# 3Dheater1.net
KiCad netlist of a schematic drawn in Altium Designer
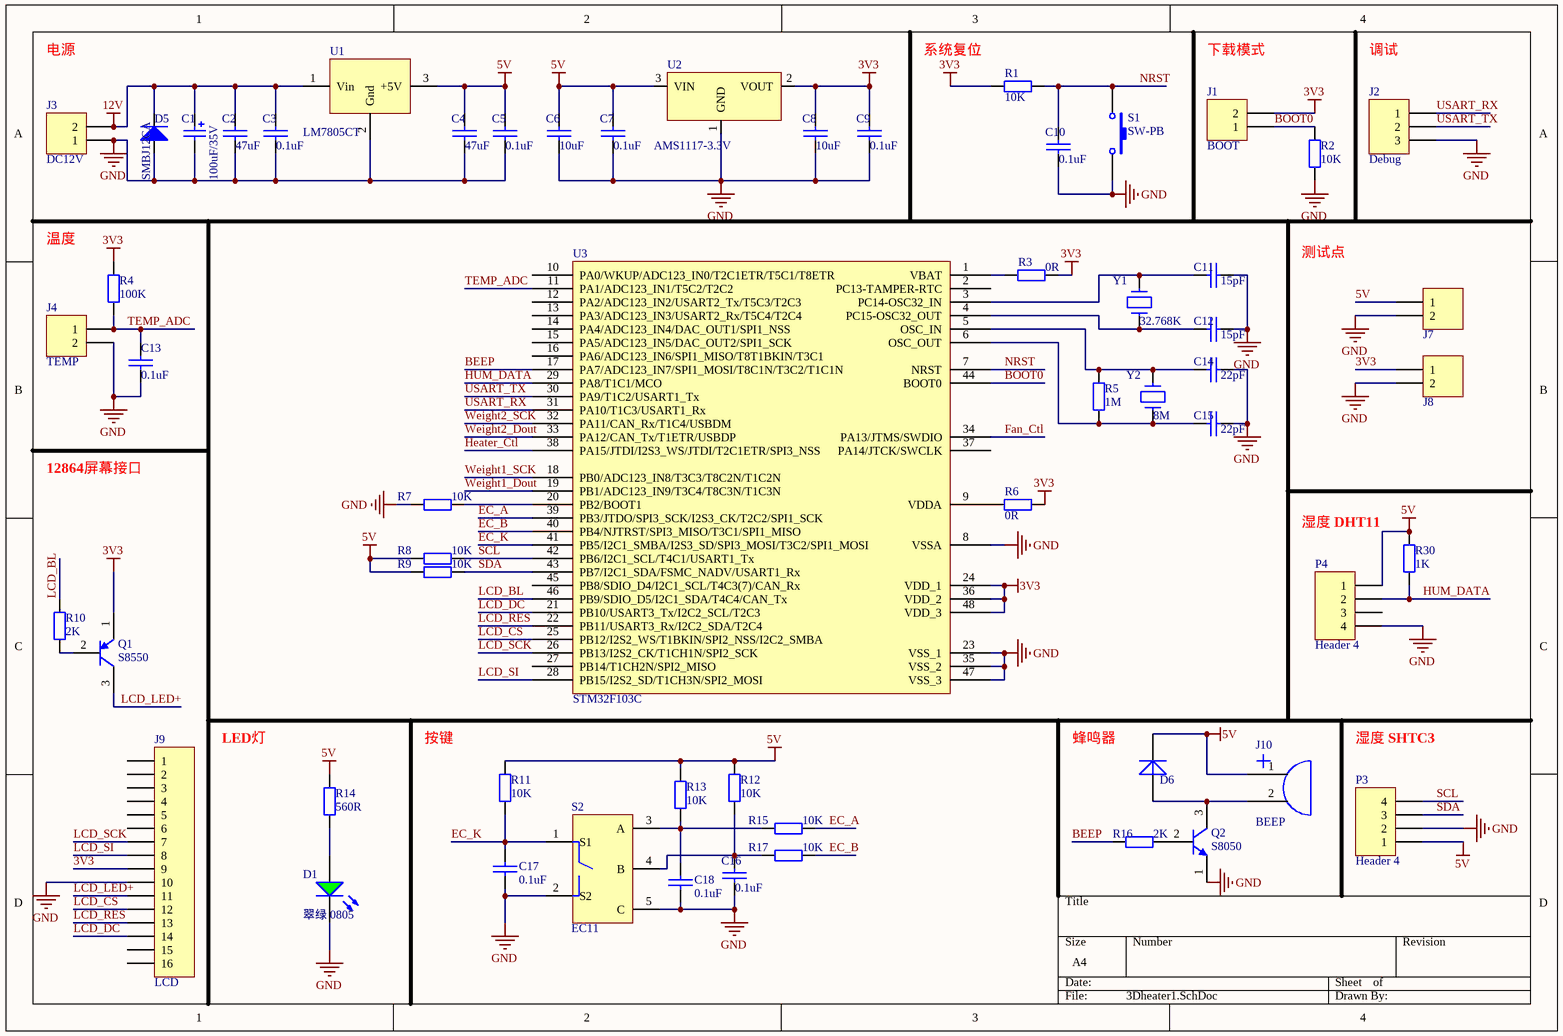
[diagram p0: 3Dheater1.SchDoc]

(export (version "E")
  (design (tool "Eeschema 10.0.6"))
  (components
    (comp (ref "C1")
      (value "100uF/35V")
      (footprint "3Dheater:ELCO Case D")
      (description "RO ELCO 100uF 20% 35V CASE-D EEEFP PAN")
      (libsource (lib "3Dheater") (part "Capacitor Polarity"))
    )
    (comp (ref "C2")
      (value "47uF")
      (footprint "1206")
      (description "Capacitor")
      (libsource (lib "Miscellaneous Devices") (part "CAP"))
    )
    (comp (ref "C3")
      (value "0.1uF")
      (footprint "C0805")
      (description "Capacitor")
      (libsource (lib "Miscellaneous Devices") (part "CAP"))
    )
    (comp (ref "C4")
      (value "47uF")
      (footprint "C0805")
      (description "Capacitor")
      (libsource (lib "Miscellaneous Devices") (part "CAP"))
    )
    (comp (ref "C5")
      (value "0.1uF")
      (footprint "C0805")
      (description "Capacitor")
      (libsource (lib "Miscellaneous Devices") (part "CAP"))
    )
    (comp (ref "C6")
      (value "10uF")
      (footprint "C0805")
      (description "Capacitor")
      (libsource (lib "Miscellaneous Devices") (part "CAP"))
    )
    (comp (ref "C7")
      (value "0.1uF")
      (footprint "C0805")
      (description "Capacitor")
      (libsource (lib "Miscellaneous Devices") (part "CAP"))
    )
    (comp (ref "C8")
      (value "10uF")
      (footprint "C0805")
      (description "Capacitor")
      (libsource (lib "Miscellaneous Devices") (part "CAP"))
    )
    (comp (ref "C9")
      (value "0.1uF")
      (footprint "C0805")
      (description "Capacitor")
      (libsource (lib "Miscellaneous Devices") (part "CAP"))
    )
    (comp (ref "C10")
      (value "0.1uF")
      (footprint "C0805")
      (description "Capacitor")
      (libsource (lib "Miscellaneous Devices") (part "CAP"))
    )
    (comp (ref "C11")
      (value "15pF")
      (footprint "C0805")
      (description "Capacitor")
      (libsource (lib "Miscellaneous Devices") (part "CAP"))
    )
    (comp (ref "C12")
      (value "15pF")
      (footprint "C0805")
      (description "Capacitor")
      (libsource (lib "Miscellaneous Devices") (part "CAP"))
    )
    (comp (ref "C13")
      (value "0.1uF")
      (footprint "C0805")
      (description "Capacitor")
      (libsource (lib "Miscellaneous Devices") (part "CAP"))
    )
    (comp (ref "C14")
      (value "22pF")
      (footprint "C0805")
      (description "Capacitor")
      (libsource (lib "Miscellaneous Devices") (part "CAP"))
    )
    (comp (ref "C15")
      (value "22pF")
      (footprint "C0805")
      (description "Capacitor")
      (libsource (lib "Miscellaneous Devices") (part "CAP"))
    )
    (comp (ref "C16")
      (value "0.1uF")
      (footprint "C0805")
      (description "Capacitor")
      (libsource (lib "Miscellaneous Devices") (part "CAP"))
    )
    (comp (ref "C17")
      (value "0.1uF")
      (footprint "C0805")
      (description "Capacitor")
      (libsource (lib "Miscellaneous Devices") (part "CAP"))
    )
    (comp (ref "C18")
      (value "0.1uF")
      (footprint "C0805")
      (description "Capacitor")
      (libsource (lib "Miscellaneous Devices") (part "CAP"))
    )
    (comp (ref "D1")
      (value "翠绿 0805")
      (footprint "0805_LED_S1")
      (description "发光二极管")
      (libsource (lib "Miscellaneous Devices LC") (part "0805 翠绿"))
    )
    (comp (ref "D5")
      (value "TVS")
      (footprint "DO214AA (SMB)")
      (description "TVS保护")
      (fields (field (name "TYPE") "SMBJ12CA") (field (name "PUBLISHER") "Altium Limited"))
      (libsource (lib "fszhang") (part "TVS"))
    )
    (comp (ref "D6")
      (value "S1G")
      (footprint "DO214AC (SMA)")
      (description "RO DIODE S1G DO-214AC")
      (libsource (lib "Database_Faber") (part "Diode"))
    )
    (comp (ref "J1")
      (value "BOOT")
      (footprint "HDR1X2")
      (description "Header, 2-Pin, Right Angle")
      (fields (field (name "PUBLISHER") "Altium Limited"))
      (libsource (lib "") (part "Header 2H_1"))
    )
    (comp (ref "J2")
      (value "Debug")
      (footprint "HDR1X3")
      (description "接插件")
      (fields (field (name "PUBLISHER") "Altium Limited"))
      (libsource (lib "fszhang") (part "Header 3"))
    )
    (comp (ref "J3")
      (value "DC12V")
      (footprint "HDR1X2_396")
      (description "接插件")
      (fields (field (name "PUBLISHER") "Altium Limited"))
      (libsource (lib "") (part "Header 2_1"))
    )
    (comp (ref "J4")
      (value "TEMP")
      (footprint "HDR1X2")
      (description "Header, 2-Pin, Right Angle")
      (fields (field (name "PUBLISHER") "Altium Limited"))
      (libsource (lib "Miscellaneous Connectors") (part "Header 2H"))
    )
    (comp (ref "J7")
      (value "Header 2")
      (footprint "HDR1X2")
      (description "接插件")
      (fields (field (name "PUBLISHER") "Altium Limited"))
      (libsource (lib "fszhang") (part "Header 2"))
    )
    (comp (ref "J8")
      (value "Header 2")
      (footprint "HDR1X2")
      (description "接插件")
      (fields (field (name "PUBLISHER") "Altium Limited"))
      (libsource (lib "fszhang") (part "Header 2"))
    )
    (comp (ref "J9")
      (value "LCD")
      (footprint "LCD12864")
      (description "Header, 16-Pin")
      (fields (field (name "PUBLISHER") "Altium Limited"))
      (libsource (lib "3Dheater") (part "Header 16"))
    )
    (comp (ref "J10")
      (value "BEEP")
      (footprint "Explorer STM32F407封装库:BELL-5")
      (description "蜂鸣器")
      (libsource (lib "fszhang") (part "BEEP"))
    )
    (comp (ref "P3")
      (value "Header 4")
      (footprint "HDR1X4")
      (description "Header, 4-Pin")
      (fields (field (name "PUBLISHER") "Altium Limited"))
      (libsource (lib "Miscellaneous Connectors") (part "Header 4"))
    )
    (comp (ref "P4")
      (value "Header 4")
      (footprint "HDR1X4")
      (description "Header, 4-Pin")
      (fields (field (name "PUBLISHER") "Altium Limited"))
      (libsource (lib "") (part "Header 4_1"))
    )
    (comp (ref "Q1")
      (value "S8550")
      (footprint "Miscellaneous Devices LC:SOT-23-3L")
      (description "PNP三极管")
      (fields (field (name "PUBLISHER") "Altium Limited"))
      (libsource (lib "fszhang") (part "S8550"))
    )
    (comp (ref "Q2")
      (value "S8050")
      (footprint "Miscellaneous Devices LC:SOT-23-3L")
      (description "NPN三极管")
      (fields (field (name "PUBLISHER") "Altium Limited"))
      (libsource (lib "fszhang") (part "S8050"))
    )
    (comp (ref "R1")
      (value "10K")
      (footprint "R0805")
      (description "贴片电阻")
      (fields (field (name "PUBLISHER") "Altium Limited"))
      (libsource (lib "") (part "Res1_1"))
    )
    (comp (ref "R2")
      (value "10K")
      (footprint "R0805")
      (description "贴片电阻")
      (fields (field (name "PUBLISHER") "Altium Limited"))
      (libsource (lib "") (part "Res1_3"))
    )
    (comp (ref "R3")
      (value "0R")
      (footprint "R0805")
      (description "贴片电阻")
      (fields (field (name "PUBLISHER") "Altium Limited"))
      (libsource (lib "") (part "Res1_1"))
    )
    (comp (ref "R4")
      (value "100K")
      (footprint "R0805")
      (description "贴片电阻")
      (fields (field (name "PUBLISHER") "Altium Limited"))
      (libsource (lib "") (part "Res1_3"))
    )
    (comp (ref "R5")
      (value "1M")
      (footprint "R0805")
      (description "贴片电阻")
      (fields (field (name "PUBLISHER") "Altium Limited"))
      (libsource (lib "") (part "Res1_2"))
    )
    (comp (ref "R6")
      (value "0R")
      (footprint "R0805")
      (description "贴片电阻")
      (fields (field (name "PUBLISHER") "Altium Limited"))
      (libsource (lib "") (part "Res1_1"))
    )
    (comp (ref "R7")
      (value "10K")
      (footprint "R0805")
      (description "贴片电阻")
      (fields (field (name "PUBLISHER") "Altium Limited"))
      (libsource (lib "") (part "Res1_1"))
    )
    (comp (ref "R8")
      (value "10K")
      (footprint "R0805")
      (description "贴片电阻")
      (fields (field (name "PUBLISHER") "Altium Limited"))
      (libsource (lib "fszhang") (part "Res1"))
    )
    (comp (ref "R9")
      (value "10K")
      (footprint "R0805")
      (description "贴片电阻")
      (fields (field (name "PUBLISHER") "Altium Limited"))
      (libsource (lib "fszhang") (part "Res1"))
    )
    (comp (ref "R10")
      (value "2K")
      (footprint "R0805")
      (description "贴片电阻")
      (fields (field (name "PUBLISHER") "Altium Limited"))
      (libsource (lib "") (part "Res1_3"))
    )
    (comp (ref "R11")
      (value "10K")
      (footprint "R0805")
      (description "贴片电阻")
      (fields (field (name "PUBLISHER") "Altium Limited"))
      (libsource (lib "") (part "Res1_2"))
    )
    (comp (ref "R12")
      (value "10K")
      (footprint "R0805")
      (description "贴片电阻")
      (fields (field (name "PUBLISHER") "Altium Limited"))
      (libsource (lib "") (part "Res1_2"))
    )
    (comp (ref "R13")
      (value "10K")
      (footprint "R0805")
      (description "贴片电阻")
      (fields (field (name "PUBLISHER") "Altium Limited"))
      (libsource (lib "") (part "Res1_2"))
    )
    (comp (ref "R14")
      (value "560R")
      (footprint "R0805")
      (description "贴片电阻")
      (fields (field (name "PUBLISHER") "Altium Limited"))
      (libsource (lib "") (part "Res1_2"))
    )
    (comp (ref "R15")
      (value "10K")
      (footprint "R0805")
      (description "贴片电阻")
      (fields (field (name "PUBLISHER") "Altium Limited"))
      (libsource (lib "") (part "Res1_1"))
    )
    (comp (ref "R16")
      (value "2K")
      (footprint "R0805")
      (description "贴片电阻")
      (fields (field (name "PUBLISHER") "Altium Limited"))
      (libsource (lib "") (part "Res1_1"))
    )
    (comp (ref "R17")
      (value "10K")
      (footprint "R0805")
      (description "贴片电阻")
      (fields (field (name "PUBLISHER") "Altium Limited"))
      (libsource (lib "") (part "Res1_1"))
    )
    (comp (ref "R30")
      (value "1K")
      (footprint "R0805")
      (description "贴片电阻")
      (fields (field (name "PUBLISHER") "Altium Limited"))
      (libsource (lib "") (part "Res1_3"))
    )
    (comp (ref "S1")
      (value "SW-PB")
      (footprint "SW-PB2")
      (description "微动开关")
      (fields (field (name "PUBLISHER") "Altium Limited"))
      (libsource (lib "fszhang") (part "SW-PB"))
    )
    (comp (ref "S2")
      (value "EC11")
      (footprint "EC11")
      (description "旋转编码器")
      (libsource (lib "liuxiaolong") (part "EC11"))
    )
    (comp (ref "U1")
      (value "LM7805CT")
      (footprint "TO-252-2-180")
      (libsource (lib "3Dheater") (part "LM7805CT"))
    )
    (comp (ref "U2")
      (value "AMS1117-3.3V")
      (footprint "Miscellaneous Devices LC:SOT-223")
      (libsource (lib "Miscellaneous Devices") (part "LM1117"))
    )
    (comp (ref "U3")
      (value "STM32F103C")
      (footprint "LQFP48_L")
      (description "STM32单片机48引脚")
      (libsource (lib "fszhang") (part "STM32F103C"))
    )
    (comp (ref "Y1")
      (value "32.768K")
      (footprint "XTAL32")
      (description "Crystal")
      (libsource (lib "Miscellaneous Devices") (part "CRYSTAL"))
    )
    (comp (ref "Y2")
      (value "8M")
      (footprint "XTAL_US")
      (description "Crystal")
      (libsource (lib "Miscellaneous Devices") (part "CRYSTAL"))
    )
  )
  (nets
    (net (code "1") (name "/BEEP") (class "Default")
      (node (ref "R16") (pin "2") (pinfunction "2_2") (pintype "passive"))
      (node (ref "U3") (pin "17") (pinfunction "PA7/ADC123_IN7/SPI1_MOSI/T8C1N/T3C2/T1C1N_17") (pintype "passive"))
    )
    (net (code "2") (name "/BOOT0") (class "Default")
      (node (ref "J1") (pin "1") (pinfunction "1_1") (pintype "passive"))
      (node (ref "R2") (pin "1") (pinfunction "1_1") (pintype "passive"))
      (node (ref "U3") (pin "44") (pinfunction "BOOT0_44") (pintype "passive"))
    )
    (net (code "3") (name "/EC_A") (class "Default")
      (node (ref "R15") (pin "1") (pinfunction "1_1") (pintype "passive"))
      (node (ref "U3") (pin "39") (pinfunction "PB3/JTDO/SPI3_SCK/I2S3_CK/T2C2/SPI1_SCK_39") (pintype "passive"))
    )
    (net (code "4") (name "/EC_B") (class "Default")
      (node (ref "R17") (pin "1") (pinfunction "1_1") (pintype "passive"))
      (node (ref "U3") (pin "40") (pinfunction "PB4/NJTRST/SPI3_MISO/T3C1/SPI1_MISO_40") (pintype "passive"))
    )
    (net (code "5") (name "/EC_K") (class "Default")
      (node (ref "C17") (pin "2") (pinfunction "2_2") (pintype "passive"))
      (node (ref "R11") (pin "1") (pinfunction "1_1") (pintype "passive"))
      (node (ref "S2") (pin "1") (pinfunction "S1_1") (pintype "passive"))
      (node (ref "U3") (pin "41") (pinfunction "PB5/I2C1_SMBA/I2S3_SD/SPI3_MOSI/T3C2/SPI1_MOSI_41") (pintype "passive"))
    )
    (net (code "6") (name "/Fan_Ctl") (class "Default")
      (node (ref "U3") (pin "34") (pinfunction "PA13/JTMS/SWDIO_34") (pintype "passive"))
    )
    (net (code "7") (name "/HUM_DATA") (class "Default")
      (node (ref "P4") (pin "2") (pinfunction "2_2") (pintype "passive"))
      (node (ref "R30") (pin "2") (pinfunction "2_2") (pintype "passive"))
      (node (ref "U3") (pin "29") (pinfunction "PA8/T1C1/MCO_29") (pintype "passive"))
    )
    (net (code "8") (name "/Heater_Ctl") (class "Default")
      (node (ref "U3") (pin "38") (pinfunction "PA15/JTDI/I2S3_WS/JTDI/T2C1ETR/SPI3_NSS_38") (pintype "passive"))
    )
    (net (code "9") (name "/LCD_BL") (class "Default")
      (node (ref "R10") (pin "1") (pinfunction "1_1") (pintype "passive"))
      (node (ref "U3") (pin "46") (pinfunction "PB9/SDIO_D5/I2C1_SDA/T4C4/CAN_Tx_46") (pintype "passive"))
    )
    (net (code "10") (name "/LCD_CS") (class "Default")
      (node (ref "J9") (pin "12") (pinfunction "12_12") (pintype "passive"))
      (node (ref "U3") (pin "25") (pinfunction "PB12/I2S2_WS/T1BKIN/SPI2_NSS/I2C2_SMBA_25") (pintype "passive"))
    )
    (net (code "11") (name "/LCD_DC") (class "Default")
      (node (ref "J9") (pin "14") (pinfunction "14_14") (pintype "passive"))
      (node (ref "U3") (pin "21") (pinfunction "PB10/USART3_Tx/I2C2_SCL/T2C3_21") (pintype "passive"))
    )
    (net (code "12") (name "/LCD_LED+") (class "Default")
      (node (ref "J9") (pin "11") (pinfunction "11_11") (pintype "passive"))
      (node (ref "Q1") (pin "3") (pinfunction "C_3") (pintype "passive"))
    )
    (net (code "13") (name "/LCD_RES") (class "Default")
      (node (ref "J9") (pin "13") (pinfunction "13_13") (pintype "passive"))
      (node (ref "U3") (pin "22") (pinfunction "PB11/USART3_Rx/I2C2_SDA/T2C4_22") (pintype "passive"))
    )
    (net (code "14") (name "/LCD_SCK") (class "Default")
      (node (ref "J9") (pin "7") (pinfunction "7_7") (pintype "passive"))
      (node (ref "U3") (pin "26") (pinfunction "PB13/I2S2_CK/T1CH1N/SPI2_SCK_26") (pintype "passive"))
    )
    (net (code "15") (name "/LCD_SI") (class "Default")
      (node (ref "J9") (pin "8") (pinfunction "8_8") (pintype "passive"))
      (node (ref "U3") (pin "28") (pinfunction "PB15/I2S2_SD/T1CH3N/SPI2_MOSI_28") (pintype "passive"))
    )
    (net (code "16") (name "/NRST") (class "Default")
      (node (ref "C10") (pin "2") (pinfunction "2_2") (pintype "passive"))
      (node (ref "R1") (pin "1") (pinfunction "1_1") (pintype "passive"))
      (node (ref "S1") (pin "1") (pinfunction "1_1") (pintype "passive"))
      (node (ref "U3") (pin "7") (pinfunction "NRST_7") (pintype "passive"))
    )
    (net (code "17") (name "/SCL") (class "Default")
      (node (ref "P3") (pin "4") (pinfunction "4_4") (pintype "passive"))
      (node (ref "R8") (pin "2") (pinfunction "2_2") (pintype "passive"))
      (node (ref "U3") (pin "42") (pinfunction "PB6/I2C1_SCL/T4C1/USART1_Tx_42") (pintype "passive"))
    )
    (net (code "18") (name "/SDA") (class "Default")
      (node (ref "P3") (pin "3") (pinfunction "3_3") (pintype "passive"))
      (node (ref "R9") (pin "2") (pinfunction "2_2") (pintype "passive"))
      (node (ref "U3") (pin "43") (pinfunction "PB7/I2C1_SDA/FSMC_NADV/USART1_Rx_43") (pintype "passive"))
    )
    (net (code "19") (name "/TEMP_ADC") (class "Default")
      (node (ref "C13") (pin "2") (pinfunction "2_2") (pintype "passive"))
      (node (ref "J4") (pin "1") (pinfunction "1_1") (pintype "passive"))
      (node (ref "R4") (pin "2") (pinfunction "2_2") (pintype "passive"))
      (node (ref "U3") (pin "11") (pinfunction "PA1/ADC123_IN1/T5C2/T2C2_11") (pintype "passive"))
    )
    (net (code "20") (name "/USART_RX") (class "Default")
      (node (ref "J2") (pin "1") (pinfunction "1_1") (pintype "passive"))
      (node (ref "U3") (pin "31") (pinfunction "PA10/T1C3/USART1_Rx_31") (pintype "passive"))
    )
    (net (code "21") (name "/USART_TX") (class "Default")
      (node (ref "J2") (pin "2") (pinfunction "2_2") (pintype "passive"))
      (node (ref "U3") (pin "30") (pinfunction "PA9/T1C2/USART1_Tx_30") (pintype "passive"))
    )
    (net (code "22") (name "/Weight1_Dout") (class "Default")
      (node (ref "U3") (pin "19") (pinfunction "PB1/ADC123_IN9/T3C4/T8C3N/T1C3N_19") (pintype "passive"))
    )
    (net (code "23") (name "/Weight1_SCK") (class "Default")
      (node (ref "U3") (pin "18") (pinfunction "PB0/ADC123_IN8/T3C3/T8C2N/T1C2N_18") (pintype "passive"))
    )
    (net (code "24") (name "/Weight2_Dout") (class "Default")
      (node (ref "U3") (pin "33") (pinfunction "PA12/CAN_Tx/T1ETR/USBDP_33") (pintype "passive"))
    )
    (net (code "25") (name "/Weight2_SCK") (class "Default")
      (node (ref "U3") (pin "32") (pinfunction "PA11/CAN_Rx/T1C4/USBDM_32") (pintype "passive"))
    )
    (net (code "26") (name "3V3") (class "Default")
      (node (ref "C8") (pin "2") (pinfunction "2_2") (pintype "passive"))
      (node (ref "C9") (pin "2") (pinfunction "2_2") (pintype "passive"))
      (node (ref "J1") (pin "2") (pinfunction "2_2") (pintype "passive"))
      (node (ref "J8") (pin "1") (pinfunction "1_1") (pintype "passive"))
      (node (ref "J9") (pin "9") (pinfunction "9_9") (pintype "passive"))
      (node (ref "Q1") (pin "1") (pinfunction "E_1") (pintype "passive"))
      (node (ref "R1") (pin "2") (pinfunction "2_2") (pintype "passive"))
      (node (ref "R3") (pin "1") (pinfunction "1_1") (pintype "passive"))
      (node (ref "R4") (pin "1") (pinfunction "1_1") (pintype "passive"))
      (node (ref "R6") (pin "1") (pinfunction "1_1") (pintype "passive"))
      (node (ref "U2") (pin "2") (pinfunction "VOUT_2") (pintype "passive"))
      (node (ref "U3") (pin "24") (pinfunction "VDD_1_24") (pintype "passive"))
      (node (ref "U3") (pin "36") (pinfunction "VDD_2_36") (pintype "passive"))
      (node (ref "U3") (pin "48") (pinfunction "VDD_3_48") (pintype "passive"))
    )
    (net (code "27") (name "5V") (class "Default")
      (node (ref "C4") (pin "2") (pinfunction "2_2") (pintype "passive"))
      (node (ref "C5") (pin "2") (pinfunction "2_2") (pintype "passive"))
      (node (ref "C6") (pin "2") (pinfunction "2_2") (pintype "passive"))
      (node (ref "C7") (pin "2") (pinfunction "2_2") (pintype "passive"))
      (node (ref "D6") (pin "2") (pinfunction "K_2") (pintype "passive"))
      (node (ref "J10") (pin "1") (pinfunction "0_1") (pintype "passive"))
      (node (ref "J7") (pin "1") (pinfunction "1_1") (pintype "passive"))
      (node (ref "P3") (pin "1") (pinfunction "1_1") (pintype "passive"))
      (node (ref "P4") (pin "1") (pinfunction "1_1") (pintype "passive"))
      (node (ref "R11") (pin "2") (pinfunction "2_2") (pintype "passive"))
      (node (ref "R12") (pin "2") (pinfunction "2_2") (pintype "passive"))
      (node (ref "R13") (pin "2") (pinfunction "2_2") (pintype "passive"))
      (node (ref "R14") (pin "2") (pinfunction "2_2") (pintype "passive"))
      (node (ref "R30") (pin "1") (pinfunction "1_1") (pintype "passive"))
      (node (ref "R8") (pin "1") (pinfunction "1_1") (pintype "passive"))
      (node (ref "R9") (pin "1") (pinfunction "1_1") (pintype "passive"))
      (node (ref "U1") (pin "3") (pinfunction "+5V_3") (pintype "passive"))
      (node (ref "U2") (pin "3") (pinfunction "VIN_3") (pintype "passive"))
    )
    (net (code "28") (name "12V") (class "Default")
      (node (ref "C1") (pin "1") (pinfunction "1_1") (pintype "passive"))
      (node (ref "C2") (pin "2") (pinfunction "2_2") (pintype "passive"))
      (node (ref "C3") (pin "2") (pinfunction "2_2") (pintype "passive"))
      (node (ref "D5") (pin "2") (pinfunction "K_2") (pintype "passive"))
      (node (ref "J3") (pin "2") (pinfunction "2_2") (pintype "passive"))
      (node (ref "U1") (pin "1") (pinfunction "Vin_1") (pintype "passive"))
    )
    (net (code "29") (name "GND") (class "Default")
      (node (ref "C1") (pin "2") (pinfunction "2_2") (pintype "passive"))
      (node (ref "C10") (pin "1") (pinfunction "1_1") (pintype "passive"))
      (node (ref "C11") (pin "2") (pinfunction "2_2") (pintype "passive"))
      (node (ref "C12") (pin "2") (pinfunction "2_2") (pintype "passive"))
      (node (ref "C13") (pin "1") (pinfunction "1_1") (pintype "passive"))
      (node (ref "C14") (pin "2") (pinfunction "2_2") (pintype "passive"))
      (node (ref "C15") (pin "2") (pinfunction "2_2") (pintype "passive"))
      (node (ref "C16") (pin "1") (pinfunction "1_1") (pintype "passive"))
      (node (ref "C17") (pin "1") (pinfunction "1_1") (pintype "passive"))
      (node (ref "C18") (pin "1") (pinfunction "1_1") (pintype "passive"))
      (node (ref "C2") (pin "1") (pinfunction "1_1") (pintype "passive"))
      (node (ref "C3") (pin "1") (pinfunction "1_1") (pintype "passive"))
      (node (ref "C4") (pin "1") (pinfunction "1_1") (pintype "passive"))
      (node (ref "C5") (pin "1") (pinfunction "1_1") (pintype "passive"))
      (node (ref "C6") (pin "1") (pinfunction "1_1") (pintype "passive"))
      (node (ref "C7") (pin "1") (pinfunction "1_1") (pintype "passive"))
      (node (ref "C8") (pin "1") (pinfunction "1_1") (pintype "passive"))
      (node (ref "C9") (pin "1") (pinfunction "1_1") (pintype "passive"))
      (node (ref "D1") (pin "K") (pinfunction "K_K") (pintype "passive"))
      (node (ref "D5") (pin "1") (pinfunction "A_1") (pintype "passive"))
      (node (ref "J2") (pin "3") (pinfunction "3_3") (pintype "passive"))
      (node (ref "J3") (pin "1") (pinfunction "1_1") (pintype "passive"))
      (node (ref "J4") (pin "2") (pinfunction "2_2") (pintype "passive"))
      (node (ref "J7") (pin "2") (pinfunction "2_2") (pintype "passive"))
      (node (ref "J8") (pin "2") (pinfunction "2_2") (pintype "passive"))
      (node (ref "J9") (pin "10") (pinfunction "10_10") (pintype "passive"))
      (node (ref "P3") (pin "2") (pinfunction "2_2") (pintype "passive"))
      (node (ref "P4") (pin "4") (pinfunction "4_4") (pintype "passive"))
      (node (ref "Q2") (pin "1") (pinfunction "E_1") (pintype "passive"))
      (node (ref "R2") (pin "2") (pinfunction "2_2") (pintype "passive"))
      (node (ref "R7") (pin "2") (pinfunction "2_2") (pintype "passive"))
      (node (ref "S1") (pin "2") (pinfunction "2_2") (pintype "passive"))
      (node (ref "S2") (pin "2") (pinfunction "S2_2") (pintype "passive"))
      (node (ref "S2") (pin "5") (pinfunction "C_5") (pintype "passive"))
      (node (ref "U1") (pin "2") (pinfunction "Gnd_2") (pintype "passive"))
      (node (ref "U2") (pin "1") (pinfunction "GND_1") (pintype "passive"))
      (node (ref "U3") (pin "23") (pinfunction "VSS_1_23") (pintype "passive"))
      (node (ref "U3") (pin "35") (pinfunction "VSS_2_35") (pintype "passive"))
      (node (ref "U3") (pin "47") (pinfunction "VSS_3_47") (pintype "passive"))
      (node (ref "U3") (pin "8") (pinfunction "VSSA_8") (pintype "passive"))
    )
    (net (code "30") (name "Net-(D1-PadA)") (class "Default")
      (node (ref "D1") (pin "A") (pinfunction "A_A") (pintype "passive"))
      (node (ref "R14") (pin "1") (pinfunction "1_1") (pintype "passive"))
    )
    (net (code "31") (name "Net-(D6-A)") (class "Default")
      (node (ref "D6") (pin "1") (pinfunction "A_1") (pintype "passive"))
      (node (ref "J10") (pin "2") (pinfunction "1_2") (pintype "passive"))
      (node (ref "Q2") (pin "3") (pinfunction "C_3") (pintype "passive"))
    )
    (net (code "32") (name "Net-(Q1-B)") (class "Default")
      (node (ref "Q1") (pin "2") (pinfunction "B_2") (pintype "passive"))
      (node (ref "R10") (pin "2") (pinfunction "2_2") (pintype "passive"))
    )
    (net (code "33") (name "Net-(Q2-B)") (class "Default")
      (node (ref "Q2") (pin "2") (pinfunction "B_2") (pintype "passive"))
      (node (ref "R16") (pin "1") (pinfunction "1_1") (pintype "passive"))
    )
    (net (code "34") (name "Net-(S2-A)") (class "Default")
      (node (ref "C18") (pin "2") (pinfunction "2_2") (pintype "passive"))
      (node (ref "R13") (pin "1") (pinfunction "1_1") (pintype "passive"))
      (node (ref "R15") (pin "2") (pinfunction "2_2") (pintype "passive"))
      (node (ref "S2") (pin "3") (pinfunction "A_3") (pintype "passive"))
    )
    (net (code "35") (name "Net-(S2-B)") (class "Default")
      (node (ref "C16") (pin "2") (pinfunction "2_2") (pintype "passive"))
      (node (ref "R12") (pin "1") (pinfunction "1_1") (pintype "passive"))
      (node (ref "R17") (pin "2") (pinfunction "2_2") (pintype "passive"))
      (node (ref "S2") (pin "4") (pinfunction "B_4") (pintype "passive"))
    )
    (net (code "36") (name "Net-(U3-OSC_IN)") (class "Default")
      (node (ref "C14") (pin "1") (pinfunction "1_1") (pintype "passive"))
      (node (ref "R5") (pin "2") (pinfunction "2_2") (pintype "passive"))
      (node (ref "U3") (pin "5") (pinfunction "OSC_IN_5") (pintype "passive"))
      (node (ref "Y2") (pin "2") (pinfunction "2_2") (pintype "passive"))
    )
    (net (code "37") (name "Net-(U3-OSC_OUT)") (class "Default")
      (node (ref "C15") (pin "1") (pinfunction "1_1") (pintype "passive"))
      (node (ref "R5") (pin "1") (pinfunction "1_1") (pintype "passive"))
      (node (ref "U3") (pin "6") (pinfunction "OSC_OUT_6") (pintype "passive"))
      (node (ref "Y2") (pin "1") (pinfunction "1_1") (pintype "passive"))
    )
    (net (code "38") (name "Net-(U3-PB2{slash}BOOT1)") (class "Default")
      (node (ref "R7") (pin "1") (pinfunction "1_1") (pintype "passive"))
      (node (ref "U3") (pin "20") (pinfunction "PB2/BOOT1_20") (pintype "passive"))
    )
    (net (code "39") (name "Net-(U3-PC14-OSC32_IN)") (class "Default")
      (node (ref "C11") (pin "1") (pinfunction "1_1") (pintype "passive"))
      (node (ref "U3") (pin "3") (pinfunction "PC14-OSC32_IN_3") (pintype "passive"))
      (node (ref "Y1") (pin "2") (pinfunction "2_2") (pintype "passive"))
    )
    (net (code "40") (name "Net-(U3-PC15-OSC32_OUT)") (class "Default")
      (node (ref "C12") (pin "1") (pinfunction "1_1") (pintype "passive"))
      (node (ref "U3") (pin "4") (pinfunction "PC15-OSC32_OUT_4") (pintype "passive"))
      (node (ref "Y1") (pin "1") (pinfunction "1_1") (pintype "passive"))
    )
    (net (code "41") (name "Net-(U3-VBAT)") (class "Default")
      (node (ref "R3") (pin "2") (pinfunction "2_2") (pintype "passive"))
      (node (ref "U3") (pin "1") (pinfunction "VBAT_1") (pintype "passive"))
    )
    (net (code "42") (name "Net-(U3-VDDA)") (class "Default")
      (node (ref "R6") (pin "2") (pinfunction "2_2") (pintype "passive"))
      (node (ref "U3") (pin "9") (pinfunction "VDDA_9") (pintype "passive"))
    )
    (net (code "43") (name "unconnected-(J9-Pad1)") (class "Default")
      (node (ref "J9") (pin "1") (pinfunction "1_1") (pintype "passive"))
    )
    (net (code "44") (name "unconnected-(J9-Pad2)") (class "Default")
      (node (ref "J9") (pin "2") (pinfunction "2_2") (pintype "passive"))
    )
    (net (code "45") (name "unconnected-(J9-Pad3)") (class "Default")
      (node (ref "J9") (pin "3") (pinfunction "3_3") (pintype "passive"))
    )
    (net (code "46") (name "unconnected-(J9-Pad4)") (class "Default")
      (node (ref "J9") (pin "4") (pinfunction "4_4") (pintype "passive"))
    )
    (net (code "47") (name "unconnected-(J9-Pad5)") (class "Default")
      (node (ref "J9") (pin "5") (pinfunction "5_5") (pintype "passive"))
    )
    (net (code "48") (name "unconnected-(J9-Pad6)") (class "Default")
      (node (ref "J9") (pin "6") (pinfunction "6_6") (pintype "passive"))
    )
    (net (code "49") (name "unconnected-(J9-Pad15)") (class "Default")
      (node (ref "J9") (pin "15") (pinfunction "15_15") (pintype "passive"))
    )
    (net (code "50") (name "unconnected-(J9-Pad16)") (class "Default")
      (node (ref "J9") (pin "16") (pinfunction "16_16") (pintype "passive"))
    )
    (net (code "51") (name "unconnected-(P4-Pad3)") (class "Default")
      (node (ref "P4") (pin "3") (pinfunction "3_3") (pintype "passive"))
    )
    (net (code "52") (name "unconnected-(U3-PA0{slash}WKUP{slash}ADC123_IN0{slash}T2C1ETR{slash}T5C1{slash}T8ETR-Pad10)") (class "Default")
      (node (ref "U3") (pin "10") (pinfunction "PA0/WKUP/ADC123_IN0/T2C1ETR/T5C1/T8ETR_10") (pintype "passive"))
    )
    (net (code "53") (name "unconnected-(U3-PA2{slash}ADC123_IN2{slash}USART2_Tx{slash}T5C3{slash}T2C3-Pad12)") (class "Default")
      (node (ref "U3") (pin "12") (pinfunction "PA2/ADC123_IN2/USART2_Tx/T5C3/T2C3_12") (pintype "passive"))
    )
    (net (code "54") (name "unconnected-(U3-PA3{slash}ADC123_IN3{slash}USART2_Rx{slash}T5C4{slash}T2C4-Pad13)") (class "Default")
      (node (ref "U3") (pin "13") (pinfunction "PA3/ADC123_IN3/USART2_Rx/T5C4/T2C4_13") (pintype "passive"))
    )
    (net (code "55") (name "unconnected-(U3-PA4{slash}ADC123_IN4{slash}DAC_OUT1{slash}SPI1_NSS-Pad14)") (class "Default")
      (node (ref "U3") (pin "14") (pinfunction "PA4/ADC123_IN4/DAC_OUT1/SPI1_NSS_14") (pintype "passive"))
    )
    (net (code "56") (name "unconnected-(U3-PA5{slash}ADC123_IN5{slash}DAC_OUT2{slash}SPI1_SCK-Pad15)") (class "Default")
      (node (ref "U3") (pin "15") (pinfunction "PA5/ADC123_IN5/DAC_OUT2/SPI1_SCK_15") (pintype "passive"))
    )
    (net (code "57") (name "unconnected-(U3-PA6{slash}ADC123_IN6{slash}SPI1_MISO{slash}T8T1BKIN{slash}T3C1-Pad16)") (class "Default")
      (node (ref "U3") (pin "16") (pinfunction "PA6/ADC123_IN6/SPI1_MISO/T8T1BKIN/T3C1_16") (pintype "passive"))
    )
    (net (code "58") (name "unconnected-(U3-PA14{slash}JTCK{slash}SWCLK-Pad37)") (class "Default")
      (node (ref "U3") (pin "37") (pinfunction "PA14/JTCK/SWCLK_37") (pintype "passive"))
    )
    (net (code "59") (name "unconnected-(U3-PB8{slash}SDIO_D4{slash}I2C1_SCL{slash}T4C3(7){slash}CAN_Rx-Pad45)") (class "Default")
      (node (ref "U3") (pin "45") (pinfunction "PB8/SDIO_D4/I2C1_SCL/T4C3(7)/CAN_Rx_45") (pintype "passive"))
    )
    (net (code "60") (name "unconnected-(U3-PB14{slash}T1CH2N{slash}SPI2_MISO-Pad27)") (class "Default")
      (node (ref "U3") (pin "27") (pinfunction "PB14/T1CH2N/SPI2_MISO_27") (pintype "passive"))
    )
    (net (code "61") (name "unconnected-(U3-PC13-TAMPER-RTC-Pad2)") (class "Default")
      (node (ref "U3") (pin "2") (pinfunction "PC13-TAMPER-RTC_2") (pintype "passive"))
    )
  )
)
